# temp_sensor.net
KiCad netlist of a schematic drawn in EAGLE
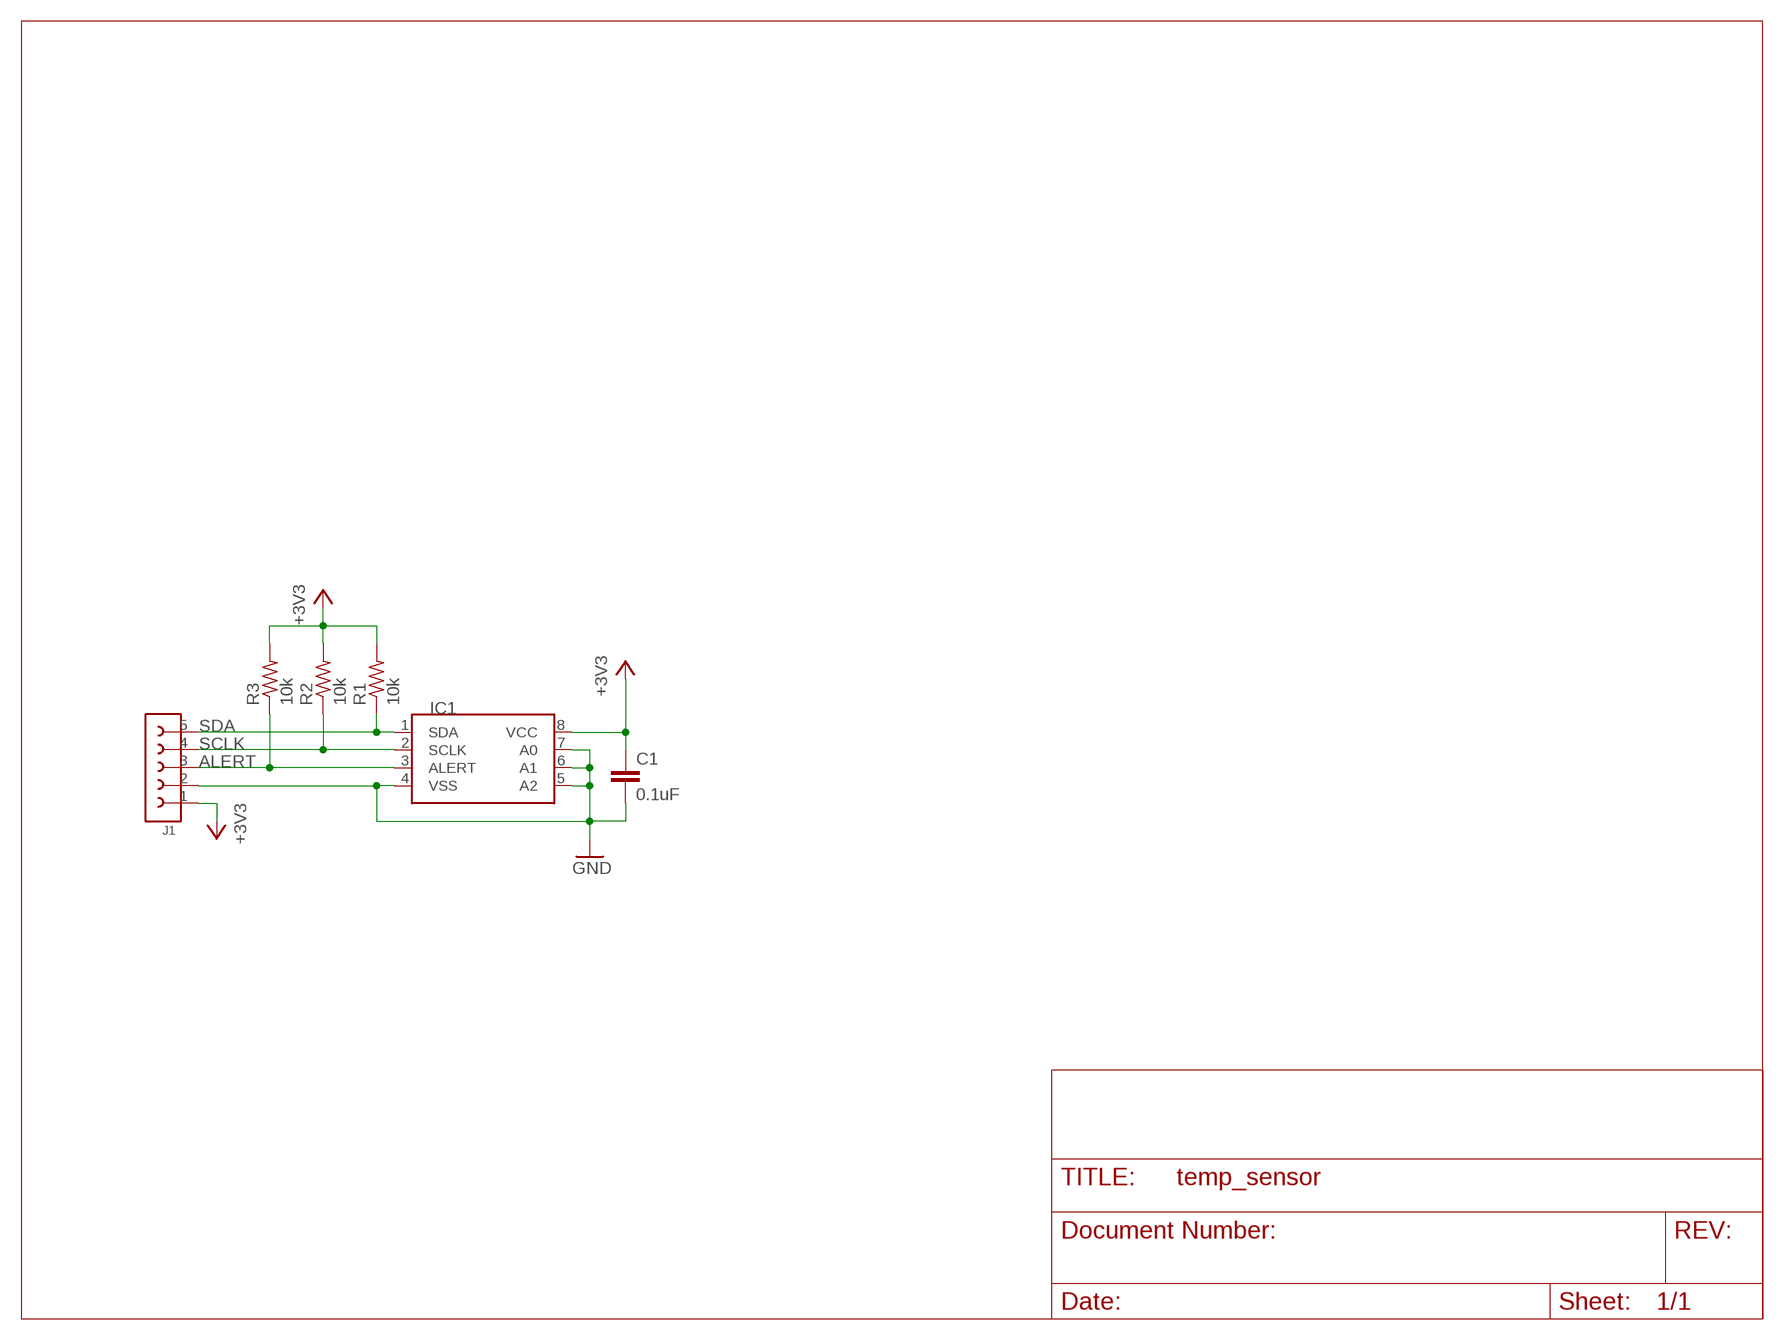
[diagram p0: schematic, sheet 1]

(export (version "E")
  (design (tool "Eeschema 10.0.6"))
  (components
    (comp (ref "C1")
      (value "0.1uF")
      (footprint "eagle-import:CAPC0603")
      (fields (field (name "MANUFACTURER") "KEMET"))
      (libsource (lib "eagle-import") (part "C?CVAC0603104Z3"))
    )
    (comp (ref "IC1")
      (value "MCP9801-T-M/SN")
      (footprint "eagle-import:SOIC127P600X175-8N")
      (libsource (lib "eagle-import") (part "MCP980-M/?SN1-T"))
    )
    (comp (ref "J1")
      (value "61300511121")
      (footprint "eagle-import:PHSP254P1270X254X1154-5S")
      (libsource (lib "eagle-import") (part "6130051?1121"))
    )
    (comp (ref "R1")
      (value "10k")
      (footprint "eagle-import:RESC0603")
      (libsource (lib "eagle-import") (part "CRG?0603F10K10"))
    )
    (comp (ref "R2")
      (value "10k")
      (footprint "eagle-import:RESC0603")
      (libsource (lib "eagle-import") (part "CRG?0603F10K10"))
    )
    (comp (ref "R3")
      (value "10k")
      (footprint "eagle-import:RESC0603")
      (libsource (lib "eagle-import") (part "CRG?0603F10K10"))
    )
  )
  (nets
    (net (code "1") (name "+3V3") (class "Default")
      (node (ref "C1") (pin "1") (pinfunction "1_1") (pintype "passive"))
      (node (ref "IC1") (pin "8") (pinfunction "VCC_8") (pintype "power_in"))
      (node (ref "J1") (pin "1") (pinfunction "1_1") (pintype "passive"))
      (node (ref "R1") (pin "P$2") (pinfunction "2_P$2") (pintype "passive"))
      (node (ref "R2") (pin "P$2") (pinfunction "2_P$2") (pintype "passive"))
      (node (ref "R3") (pin "P$2") (pinfunction "2_P$2") (pintype "passive"))
    )
    (net (code "2") (name "/ALERT") (class "Default")
      (node (ref "IC1") (pin "3") (pinfunction "ALERT_3") (pintype "bidirectional"))
      (node (ref "J1") (pin "3") (pinfunction "3_3") (pintype "passive"))
      (node (ref "R3") (pin "P$1") (pinfunction "1_P$1") (pintype "passive"))
    )
    (net (code "3") (name "/SCLK") (class "Default")
      (node (ref "IC1") (pin "2") (pinfunction "SCLK_2") (pintype "bidirectional"))
      (node (ref "J1") (pin "4") (pinfunction "4_4") (pintype "passive"))
      (node (ref "R2") (pin "P$1") (pinfunction "1_P$1") (pintype "passive"))
    )
    (net (code "4") (name "/SDA") (class "Default")
      (node (ref "IC1") (pin "1") (pinfunction "SDA_1") (pintype "bidirectional"))
      (node (ref "J1") (pin "5") (pinfunction "5_5") (pintype "passive"))
      (node (ref "R1") (pin "P$1") (pinfunction "1_P$1") (pintype "passive"))
    )
    (net (code "5") (name "GND") (class "Default")
      (node (ref "C1") (pin "2") (pinfunction "2_2") (pintype "passive"))
      (node (ref "IC1") (pin "4") (pinfunction "VSS_4") (pintype "power_in"))
      (node (ref "IC1") (pin "5") (pinfunction "A2_5") (pintype "bidirectional"))
      (node (ref "IC1") (pin "6") (pinfunction "A1_6") (pintype "bidirectional"))
      (node (ref "IC1") (pin "7") (pinfunction "A0_7") (pintype "bidirectional"))
      (node (ref "J1") (pin "2") (pinfunction "2_2") (pintype "passive"))
    )
  )
)
